# F7VO006ICD7FAPK_1.net
KiCad netlist of a schematic drawn in EAGLE
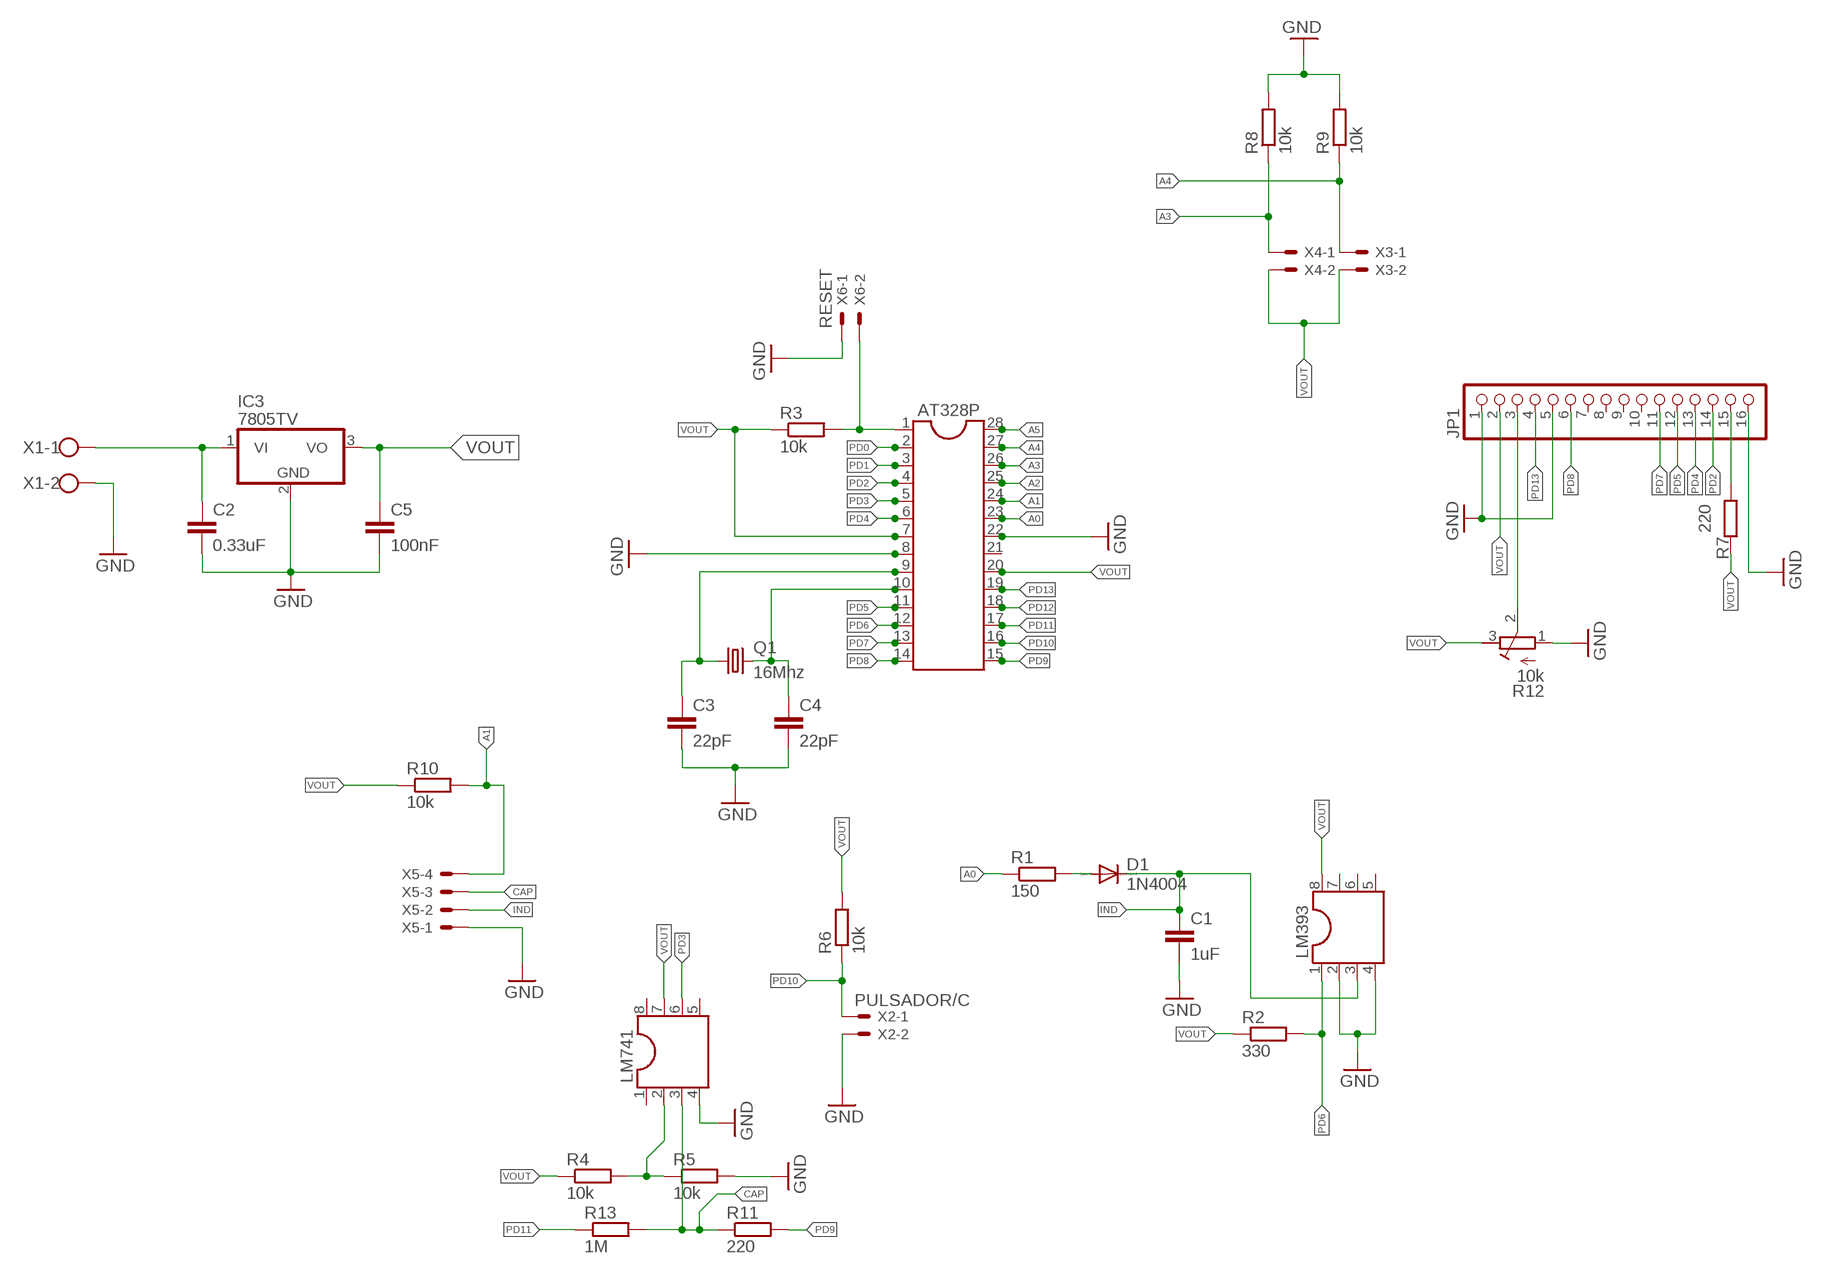
[diagram p0: schematic, sheet 1]

(export (version "E")
  (design (tool "Eeschema 10.0.6"))
  (components
    (comp (ref "AT328P")
      (value "DIL28-3")
      (footprint "eagle-import:DIL28-3")
      (libsource (lib "eagle-import") (part "DIL28-3"))
    )
    (comp (ref "C1")
      (value "1uF")
      (footprint "eagle-import:C050-024X044")
      (libsource (lib "eagle-import") (part "C-EU050-024X044"))
    )
    (comp (ref "C2")
      (value "0.33uF")
      (footprint "eagle-import:C050-024X044")
      (libsource (lib "eagle-import") (part "C-EU050-024X044"))
    )
    (comp (ref "C3")
      (value "22pF")
      (footprint "eagle-import:C025-030X050")
      (libsource (lib "eagle-import") (part "C-EU025-030X050"))
    )
    (comp (ref "C4")
      (value "22pF")
      (footprint "eagle-import:C025-030X050")
      (libsource (lib "eagle-import") (part "C-EU025-030X050"))
    )
    (comp (ref "C5")
      (value "100nF")
      (footprint "eagle-import:C025-030X050")
      (libsource (lib "eagle-import") (part "C-EU025-030X050"))
    )
    (comp (ref "D1")
      (value "1N4004")
      (footprint "eagle-import:DO41-10")
      (libsource (lib "eagle-import") (part "1N4004"))
    )
    (comp (ref "IC3")
      (value "7805TV")
      (footprint "eagle-import:TO220V")
      (libsource (lib "eagle-import") (part "78TV05"))
    )
    (comp (ref "JP1")
      (value "PINHD-1X16")
      (footprint "eagle-import:1X16")
      (libsource (lib "eagle-import") (part "PINHD-1X16"))
    )
    (comp (ref "LM393")
      (value "DIL8S")
      (footprint "eagle-import:SOCKET-08")
      (libsource (lib "eagle-import") (part "DIL8S"))
    )
    (comp (ref "LM741")
      (value "DIL8S")
      (footprint "eagle-import:SOCKET-08")
      (libsource (lib "eagle-import") (part "DIL8S"))
    )
    (comp (ref "Q1")
      (value "16Mhz")
      (footprint "eagle-import:HC49_S")
      (libsource (lib "eagle-import") (part "CRYSTALHC49S"))
    )
    (comp (ref "R1")
      (value "150")
      (footprint "eagle-import:0207_7")
      (libsource (lib "eagle-import") (part "R-EU_0207/7"))
    )
    (comp (ref "R2")
      (value "330")
      (footprint "eagle-import:0207_7")
      (libsource (lib "eagle-import") (part "R-EU_0207/7"))
    )
    (comp (ref "R3")
      (value "10k")
      (footprint "eagle-import:0207_7")
      (libsource (lib "eagle-import") (part "R-EU_0207/7"))
    )
    (comp (ref "R4")
      (value "10k")
      (footprint "eagle-import:0207_7")
      (libsource (lib "eagle-import") (part "R-EU_0207/7"))
    )
    (comp (ref "R5")
      (value "10k")
      (footprint "eagle-import:0207_7")
      (libsource (lib "eagle-import") (part "R-EU_0207/7"))
    )
    (comp (ref "R6")
      (value "10k")
      (footprint "eagle-import:0207_7")
      (libsource (lib "eagle-import") (part "R-EU_0207/7"))
    )
    (comp (ref "R7")
      (value "220")
      (footprint "eagle-import:0207_7")
      (libsource (lib "eagle-import") (part "R-EU_0207/7"))
    )
    (comp (ref "R8")
      (value "10k")
      (footprint "eagle-import:0207_7")
      (libsource (lib "eagle-import") (part "R-EU_0207/7"))
    )
    (comp (ref "R9")
      (value "10k")
      (footprint "eagle-import:0207_7")
      (libsource (lib "eagle-import") (part "R-EU_0207/7"))
    )
    (comp (ref "R10")
      (value "10k")
      (footprint "eagle-import:0207_7")
      (libsource (lib "eagle-import") (part "R-EU_0207/7"))
    )
    (comp (ref "R11")
      (value "220")
      (footprint "eagle-import:0207_7")
      (libsource (lib "eagle-import") (part "R-EU_0207/7"))
    )
    (comp (ref "R12")
      (value "10k")
      (footprint "eagle-import:RTRIM64W")
      (libsource (lib "eagle-import") (part "R-TRIMM64W"))
    )
    (comp (ref "R13")
      (value "1M")
      (footprint "eagle-import:0207_7")
      (libsource (lib "eagle-import") (part "R-EU_0207/7"))
    )
    (comp (ref "X1")
      (value "W237-102")
      (footprint "eagle-import:W237-102")
      (fields (field (name "MPN") "237-102"))
      (libsource (lib "eagle-import") (part "W237-102"))
    )
    (comp (ref "X2")
      (value "PULSADOR/C")
      (footprint "eagle-import:22-23-2021")
      (fields (field (name "MF") "MOLEX") (field (name "MPN") "22-23-2021"))
      (libsource (lib "eagle-import") (part "22-23-2021"))
    )
    (comp (ref "X3")
      (value "22-23-2021")
      (footprint "eagle-import:22-23-2021")
      (fields (field (name "MF") "MOLEX"))
      (libsource (lib "eagle-import") (part "22-23-2021"))
    )
    (comp (ref "X4")
      (value "22-23-2021")
      (footprint "eagle-import:22-23-2021")
      (fields (field (name "MF") "MOLEX"))
      (libsource (lib "eagle-import") (part "22-23-2021"))
    )
    (comp (ref "X5")
      (value "22-23-2041")
      (footprint "eagle-import:22-23-2041")
      (fields (field (name "MF") "MOLEX"))
      (libsource (lib "eagle-import") (part "22-23-2041"))
    )
    (comp (ref "X6")
      (value "RESET")
      (footprint "eagle-import:22-23-2021")
      (fields (field (name "MF") "MOLEX") (field (name "MPN") "22-23-2021"))
      (libsource (lib "eagle-import") (part "22-23-2021"))
    )
  )
  (nets
    (net (code "1") (name "A0") (class "Default")
      (node (ref "AT328P") (pin "23") (pinfunction "23_23") (pintype "passive"))
      (node (ref "R1") (pin "1") (pinfunction "1_1") (pintype "passive"))
    )
    (net (code "2") (name "A1") (class "Default")
      (node (ref "AT328P") (pin "24") (pinfunction "24_24") (pintype "passive"))
      (node (ref "R10") (pin "2") (pinfunction "2_2") (pintype "passive"))
      (node (ref "X5") (pin "4") (pinfunction "S_4") (pintype "passive"))
    )
    (net (code "3") (name "A2") (class "Default")
      (node (ref "AT328P") (pin "25") (pinfunction "25_25") (pintype "passive"))
    )
    (net (code "4") (name "A3") (class "Default")
      (node (ref "AT328P") (pin "26") (pinfunction "26_26") (pintype "passive"))
      (node (ref "R8") (pin "1") (pinfunction "1_1") (pintype "passive"))
      (node (ref "X4") (pin "1") (pinfunction "S_1") (pintype "passive"))
    )
    (net (code "5") (name "A4") (class "Default")
      (node (ref "AT328P") (pin "27") (pinfunction "27_27") (pintype "passive"))
      (node (ref "R9") (pin "1") (pinfunction "1_1") (pintype "passive"))
      (node (ref "X3") (pin "1") (pinfunction "S_1") (pintype "passive"))
    )
    (net (code "6") (name "A5") (class "Default")
      (node (ref "AT328P") (pin "28") (pinfunction "28_28") (pintype "passive"))
    )
    (net (code "7") (name "CAP") (class "Default")
      (node (ref "LM741") (pin "3") (pinfunction "3_3") (pintype "passive"))
      (node (ref "R11") (pin "1") (pinfunction "1_1") (pintype "passive"))
      (node (ref "R13") (pin "2") (pinfunction "2_2") (pintype "passive"))
      (node (ref "X5") (pin "3") (pinfunction "S_3") (pintype "passive"))
    )
    (net (code "8") (name "GND") (class "Default")
      (node (ref "AT328P") (pin "22") (pinfunction "22_22") (pintype "passive"))
      (node (ref "AT328P") (pin "8") (pinfunction "8_8") (pintype "passive"))
      (node (ref "C1") (pin "2") (pinfunction "2_2") (pintype "passive"))
      (node (ref "C2") (pin "2") (pinfunction "2_2") (pintype "passive"))
      (node (ref "C3") (pin "2") (pinfunction "2_2") (pintype "passive"))
      (node (ref "C4") (pin "2") (pinfunction "2_2") (pintype "passive"))
      (node (ref "C5") (pin "2") (pinfunction "2_2") (pintype "passive"))
      (node (ref "IC3") (pin "2") (pinfunction "GND_2") (pintype "passive"))
      (node (ref "JP1") (pin "1") (pinfunction "1_1") (pintype "passive"))
      (node (ref "JP1") (pin "16") (pinfunction "16_16") (pintype "passive"))
      (node (ref "JP1") (pin "5") (pinfunction "5_5") (pintype "passive"))
      (node (ref "LM393") (pin "2") (pinfunction "2_2") (pintype "passive"))
      (node (ref "LM393") (pin "4") (pinfunction "4_4") (pintype "passive"))
      (node (ref "LM741") (pin "4") (pinfunction "4_4") (pintype "passive"))
      (node (ref "R12") (pin "1") (pinfunction "A_1") (pintype "passive"))
      (node (ref "R5") (pin "2") (pinfunction "2_2") (pintype "passive"))
      (node (ref "R8") (pin "2") (pinfunction "2_2") (pintype "passive"))
      (node (ref "R9") (pin "2") (pinfunction "2_2") (pintype "passive"))
      (node (ref "X1") (pin "2") (pinfunction "KL_2") (pintype "passive"))
      (node (ref "X2") (pin "2") (pinfunction "S_2") (pintype "passive"))
      (node (ref "X5") (pin "1") (pinfunction "S_1") (pintype "passive"))
      (node (ref "X6") (pin "1") (pinfunction "S_1") (pintype "passive"))
    )
    (net (code "9") (name "IND") (class "Default")
      (node (ref "C1") (pin "1") (pinfunction "1_1") (pintype "passive"))
      (node (ref "D1") (pin "C") (pinfunction "C_C") (pintype "passive"))
      (node (ref "LM393") (pin "3") (pinfunction "3_3") (pintype "passive"))
      (node (ref "X5") (pin "2") (pinfunction "S_2") (pintype "passive"))
    )
    (net (code "10") (name "Net-(AT328P-Pad9)") (class "Default")
      (node (ref "AT328P") (pin "9") (pinfunction "9_9") (pintype "passive"))
      (node (ref "C3") (pin "1") (pinfunction "1_1") (pintype "passive"))
      (node (ref "Q1") (pin "1") (pinfunction "1_1") (pintype "passive"))
    )
    (net (code "11") (name "Net-(AT328P-Pad10)") (class "Default")
      (node (ref "AT328P") (pin "10") (pinfunction "10_10") (pintype "passive"))
      (node (ref "C4") (pin "1") (pinfunction "1_1") (pintype "passive"))
      (node (ref "Q1") (pin "2") (pinfunction "2_2") (pintype "passive"))
    )
    (net (code "12") (name "Net-(D1-PadA)") (class "Default")
      (node (ref "D1") (pin "A") (pinfunction "A_A") (pintype "passive"))
      (node (ref "R1") (pin "2") (pinfunction "2_2") (pintype "passive"))
    )
    (net (code "13") (name "Net-(IC3-VI)") (class "Default")
      (node (ref "C2") (pin "1") (pinfunction "1_1") (pintype "passive"))
      (node (ref "IC3") (pin "1") (pinfunction "VI_1") (pintype "input"))
      (node (ref "X1") (pin "1") (pinfunction "KL_1") (pintype "passive"))
    )
    (net (code "14") (name "Net-(JP1-Pad15)") (class "Default")
      (node (ref "JP1") (pin "15") (pinfunction "15_15") (pintype "passive"))
      (node (ref "R7") (pin "2") (pinfunction "2_2") (pintype "passive"))
    )
    (net (code "15") (name "Net-(LM741-Pad2)") (class "Default")
      (node (ref "LM741") (pin "2") (pinfunction "2_2") (pintype "passive"))
      (node (ref "R4") (pin "2") (pinfunction "2_2") (pintype "passive"))
      (node (ref "R5") (pin "1") (pinfunction "1_1") (pintype "passive"))
    )
    (net (code "16") (name "Net-(R12-S)") (class "Default")
      (node (ref "JP1") (pin "3") (pinfunction "3_3") (pintype "passive"))
      (node (ref "R12") (pin "2") (pinfunction "S_2") (pintype "passive"))
    )
    (net (code "17") (name "Net-(X6B-S)") (class "Default")
      (node (ref "AT328P") (pin "1") (pinfunction "1_1") (pintype "passive"))
      (node (ref "R3") (pin "2") (pinfunction "2_2") (pintype "passive"))
      (node (ref "X6") (pin "2") (pinfunction "S_2") (pintype "passive"))
    )
    (net (code "18") (name "PD0") (class "Default")
      (node (ref "AT328P") (pin "2") (pinfunction "2_2") (pintype "passive"))
    )
    (net (code "19") (name "PD1") (class "Default")
      (node (ref "AT328P") (pin "3") (pinfunction "3_3") (pintype "passive"))
    )
    (net (code "20") (name "PD2") (class "Default")
      (node (ref "AT328P") (pin "4") (pinfunction "4_4") (pintype "passive"))
      (node (ref "JP1") (pin "14") (pinfunction "14_14") (pintype "passive"))
    )
    (net (code "21") (name "PD3") (class "Default")
      (node (ref "AT328P") (pin "5") (pinfunction "5_5") (pintype "passive"))
      (node (ref "LM741") (pin "6") (pinfunction "6_6") (pintype "passive"))
    )
    (net (code "22") (name "PD4") (class "Default")
      (node (ref "AT328P") (pin "6") (pinfunction "6_6") (pintype "passive"))
      (node (ref "JP1") (pin "13") (pinfunction "13_13") (pintype "passive"))
    )
    (net (code "23") (name "PD5") (class "Default")
      (node (ref "AT328P") (pin "11") (pinfunction "11_11") (pintype "passive"))
      (node (ref "JP1") (pin "12") (pinfunction "12_12") (pintype "passive"))
    )
    (net (code "24") (name "PD6") (class "Default")
      (node (ref "AT328P") (pin "12") (pinfunction "12_12") (pintype "passive"))
      (node (ref "LM393") (pin "1") (pinfunction "1_1") (pintype "passive"))
      (node (ref "R2") (pin "2") (pinfunction "2_2") (pintype "passive"))
    )
    (net (code "25") (name "PD7") (class "Default")
      (node (ref "AT328P") (pin "13") (pinfunction "13_13") (pintype "passive"))
      (node (ref "JP1") (pin "11") (pinfunction "11_11") (pintype "passive"))
    )
    (net (code "26") (name "PD8") (class "Default")
      (node (ref "AT328P") (pin "14") (pinfunction "14_14") (pintype "passive"))
      (node (ref "JP1") (pin "6") (pinfunction "6_6") (pintype "passive"))
    )
    (net (code "27") (name "PD9") (class "Default")
      (node (ref "AT328P") (pin "15") (pinfunction "15_15") (pintype "passive"))
      (node (ref "R11") (pin "2") (pinfunction "2_2") (pintype "passive"))
    )
    (net (code "28") (name "PD10") (class "Default")
      (node (ref "AT328P") (pin "16") (pinfunction "16_16") (pintype "passive"))
      (node (ref "R6") (pin "1") (pinfunction "1_1") (pintype "passive"))
      (node (ref "X2") (pin "1") (pinfunction "S_1") (pintype "passive"))
    )
    (net (code "29") (name "PD11") (class "Default")
      (node (ref "AT328P") (pin "17") (pinfunction "17_17") (pintype "passive"))
      (node (ref "R13") (pin "1") (pinfunction "1_1") (pintype "passive"))
    )
    (net (code "30") (name "PD12") (class "Default")
      (node (ref "AT328P") (pin "18") (pinfunction "18_18") (pintype "passive"))
    )
    (net (code "31") (name "PD13") (class "Default")
      (node (ref "AT328P") (pin "19") (pinfunction "19_19") (pintype "passive"))
      (node (ref "JP1") (pin "4") (pinfunction "4_4") (pintype "passive"))
    )
    (net (code "32") (name "VOUT") (class "Default")
      (node (ref "AT328P") (pin "20") (pinfunction "20_20") (pintype "passive"))
      (node (ref "AT328P") (pin "7") (pinfunction "7_7") (pintype "passive"))
      (node (ref "C5") (pin "1") (pinfunction "1_1") (pintype "passive"))
      (node (ref "IC3") (pin "3") (pinfunction "VO_3") (pintype "passive"))
      (node (ref "JP1") (pin "2") (pinfunction "2_2") (pintype "passive"))
      (node (ref "LM393") (pin "8") (pinfunction "8_8") (pintype "passive"))
      (node (ref "LM741") (pin "7") (pinfunction "7_7") (pintype "passive"))
      (node (ref "R10") (pin "1") (pinfunction "1_1") (pintype "passive"))
      (node (ref "R12") (pin "3") (pinfunction "E_3") (pintype "passive"))
      (node (ref "R2") (pin "1") (pinfunction "1_1") (pintype "passive"))
      (node (ref "R3") (pin "1") (pinfunction "1_1") (pintype "passive"))
      (node (ref "R4") (pin "1") (pinfunction "1_1") (pintype "passive"))
      (node (ref "R6") (pin "2") (pinfunction "2_2") (pintype "passive"))
      (node (ref "R7") (pin "1") (pinfunction "1_1") (pintype "passive"))
      (node (ref "X3") (pin "2") (pinfunction "S_2") (pintype "passive"))
      (node (ref "X4") (pin "2") (pinfunction "S_2") (pintype "passive"))
    )
    (net (code "33") (name "unconnected-(AT328P-Pad21)") (class "Default")
      (node (ref "AT328P") (pin "21") (pinfunction "21_21") (pintype "passive"))
    )
    (net (code "34") (name "unconnected-(JP1-Pad7)") (class "Default")
      (node (ref "JP1") (pin "7") (pinfunction "7_7") (pintype "passive"))
    )
    (net (code "35") (name "unconnected-(JP1-Pad8)") (class "Default")
      (node (ref "JP1") (pin "8") (pinfunction "8_8") (pintype "passive"))
    )
    (net (code "36") (name "unconnected-(JP1-Pad9)") (class "Default")
      (node (ref "JP1") (pin "9") (pinfunction "9_9") (pintype "passive"))
    )
    (net (code "37") (name "unconnected-(JP1-Pad10)") (class "Default")
      (node (ref "JP1") (pin "10") (pinfunction "10_10") (pintype "passive"))
    )
    (net (code "38") (name "unconnected-(LM393-Pad5)") (class "Default")
      (node (ref "LM393") (pin "5") (pinfunction "5_5") (pintype "passive"))
    )
    (net (code "39") (name "unconnected-(LM393-Pad6)") (class "Default")
      (node (ref "LM393") (pin "6") (pinfunction "6_6") (pintype "passive"))
    )
    (net (code "40") (name "unconnected-(LM393-Pad7)") (class "Default")
      (node (ref "LM393") (pin "7") (pinfunction "7_7") (pintype "passive"))
    )
    (net (code "41") (name "unconnected-(LM741-Pad1)") (class "Default")
      (node (ref "LM741") (pin "1") (pinfunction "1_1") (pintype "passive"))
    )
    (net (code "42") (name "unconnected-(LM741-Pad5)") (class "Default")
      (node (ref "LM741") (pin "5") (pinfunction "5_5") (pintype "passive"))
    )
    (net (code "43") (name "unconnected-(LM741-Pad8)") (class "Default")
      (node (ref "LM741") (pin "8") (pinfunction "8_8") (pintype "passive"))
    )
  )
)
